# MIPI2HDMI.net
KiCad netlist of a schematic drawn in EAGLE
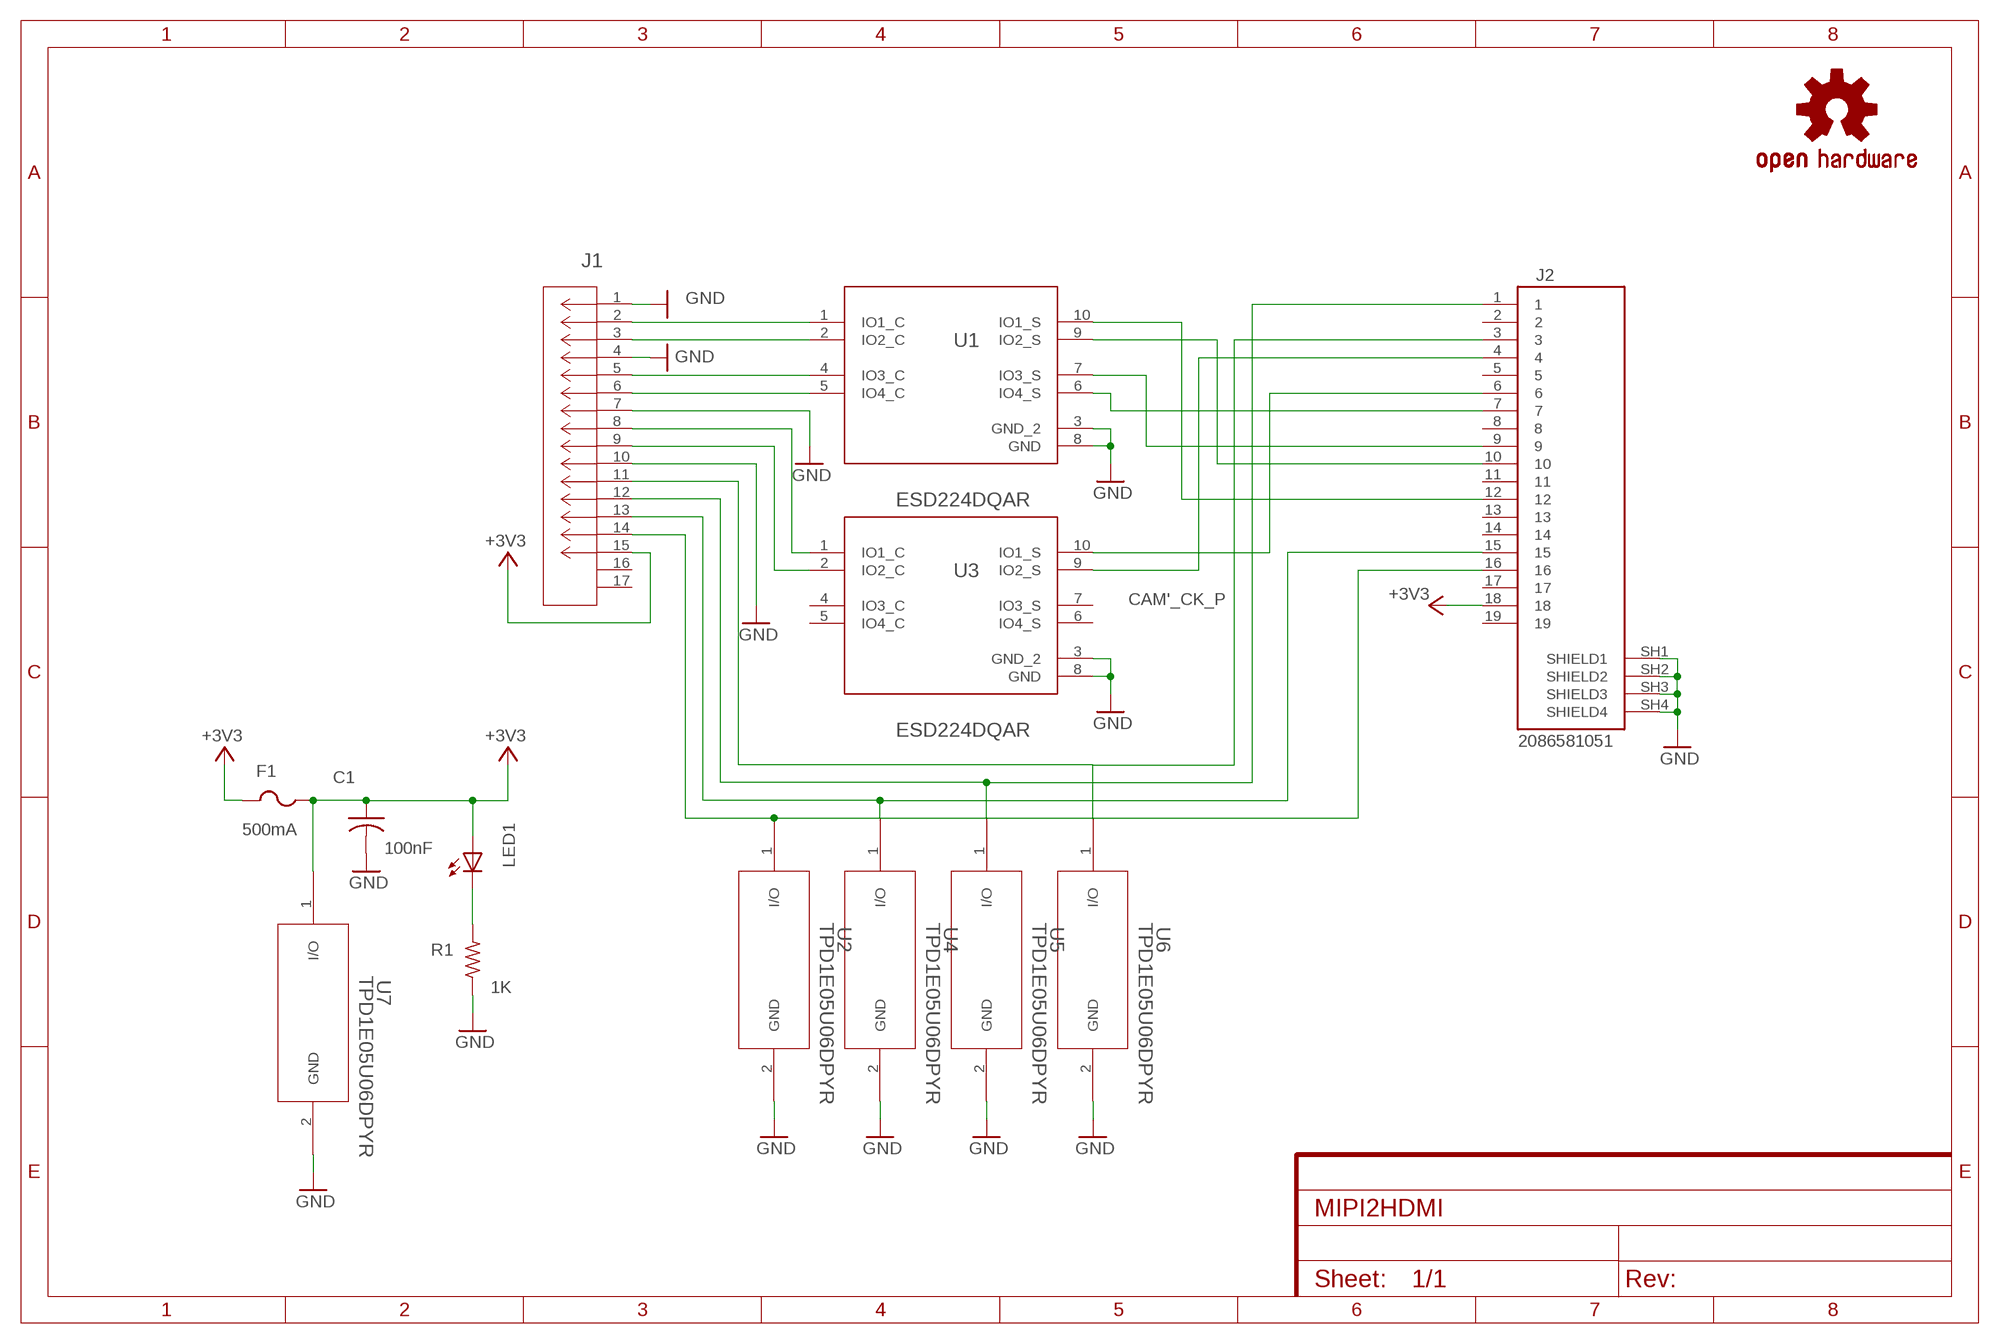
[diagram p0: schematic, sheet 1]

(export (version "E")
  (design (tool "Eeschema 10.0.6"))
  (components
    (comp (ref "C1")
      (value "100nF")
      (footprint "eagle-import:C0603")
      (libsource (lib "eagle-import") (part "C-USC0603"))
    )
    (comp (ref "F1")
      (value "500mA")
      (footprint "eagle-import:R1206")
      (libsource (lib "eagle-import") (part "PTCFUSE-1206"))
    )
    (comp (ref "J1")
      (value "1-84952-5")
      (footprint "eagle-import:CONN15_1-84952-5_TEC")
      (fields (field (name "COPYRIGHT") "Copyright (C) 2024 Ultra Librarian. All rights reserved."))
      (libsource (lib "eagle-import") (part "1-84952-5"))
    )
    (comp (ref "J2")
      (value "2086581051")
      (footprint "eagle-import:MOLEX_2086581051")
      (fields (field (name "MANUFACTURER") "Molex"))
      (libsource (lib "eagle-import") (part "2086581051"))
    )
    (comp (ref "LED1")
      (value "LEDCHIP-LED0603")
      (footprint "eagle-import:CHIP-LED0603")
      (libsource (lib "eagle-import") (part "LEDCHIP-LED0603"))
    )
    (comp (ref "LOGO1")
      (value "OSHW-LOGOM")
      (footprint "eagle-import:OSHW-LOGO-M")
      (libsource (lib "eagle-import") (part "OSHW-LOGOM"))
    )
    (comp (ref "R1")
      (value "1K")
      (footprint "eagle-import:R0603")
      (libsource (lib "eagle-import") (part "R-US_R0603"))
    )
    (comp (ref "U1")
      (value "ESD224DQAR")
      (footprint "eagle-import:DQA0010A")
      (fields (field (name "COPYRIGHT") "Copyright (C) 2024 Ultra Librarian. All rights reserved."))
      (libsource (lib "eagle-import") (part "ESD224DQAR"))
    )
    (comp (ref "U2")
      (value "TPD1E05U06DPYR")
      (footprint "eagle-import:DPY2_TEX")
      (fields (field (name "COPYRIGHT") "Copyright (C) 2024 Ultra Librarian. All rights reserved."))
      (libsource (lib "eagle-import") (part "TPD1E05U06DPYR"))
    )
    (comp (ref "U3")
      (value "ESD224DQAR")
      (footprint "eagle-import:DQA0010A")
      (fields (field (name "COPYRIGHT") "Copyright (C) 2024 Ultra Librarian. All rights reserved."))
      (libsource (lib "eagle-import") (part "ESD224DQAR"))
    )
    (comp (ref "U4")
      (value "TPD1E05U06DPYR")
      (footprint "eagle-import:DPY2_TEX")
      (fields (field (name "COPYRIGHT") "Copyright (C) 2024 Ultra Librarian. All rights reserved."))
      (libsource (lib "eagle-import") (part "TPD1E05U06DPYR"))
    )
    (comp (ref "U5")
      (value "TPD1E05U06DPYR")
      (footprint "eagle-import:DPY2_TEX")
      (fields (field (name "COPYRIGHT") "Copyright (C) 2024 Ultra Librarian. All rights reserved."))
      (libsource (lib "eagle-import") (part "TPD1E05U06DPYR"))
    )
    (comp (ref "U6")
      (value "TPD1E05U06DPYR")
      (footprint "eagle-import:DPY2_TEX")
      (fields (field (name "COPYRIGHT") "Copyright (C) 2024 Ultra Librarian. All rights reserved."))
      (libsource (lib "eagle-import") (part "TPD1E05U06DPYR"))
    )
    (comp (ref "U7")
      (value "TPD1E05U06DPYR")
      (footprint "eagle-import:DPY2_TEX")
      (fields (field (name "COPYRIGHT") "Copyright (C) 2024 Ultra Librarian. All rights reserved."))
      (libsource (lib "eagle-import") (part "TPD1E05U06DPYR"))
    )
  )
  (nets
    (net (code "1") (name "+3V3") (class "Default")
      (node (ref "C1") (pin "1") (pinfunction "1_1") (pintype "passive"))
      (node (ref "F1") (pin "1") (pinfunction "1_1") (pintype "passive"))
      (node (ref "F1") (pin "2") (pinfunction "2_2") (pintype "passive"))
      (node (ref "J1") (pin "15") (pinfunction "15_15") (pintype "passive"))
      (node (ref "J2") (pin "18") (pinfunction "18_18") (pintype "bidirectional"))
      (node (ref "LED1") (pin "A") (pinfunction "A_A") (pintype "passive"))
      (node (ref "U7") (pin "1") (pinfunction "I/O_1") (pintype "bidirectional"))
    )
    (net (code "2") (name "/CAM'_CK_P") (class "Default")
      (node (ref "J2") (pin "4") (pinfunction "4_4") (pintype "bidirectional"))
      (node (ref "U3") (pin "9") (pinfunction "IO2_S_9") (pintype "bidirectional"))
    )
    (net (code "3") (name "GND") (class "Default")
      (node (ref "C1") (pin "2") (pinfunction "2_2") (pintype "passive"))
      (node (ref "J1") (pin "1") (pinfunction "1_1") (pintype "passive"))
      (node (ref "J1") (pin "10") (pinfunction "10_10") (pintype "passive"))
      (node (ref "J1") (pin "4") (pinfunction "4_4") (pintype "passive"))
      (node (ref "J1") (pin "7") (pinfunction "7_7") (pintype "passive"))
      (node (ref "J2") (pin "SH1") (pinfunction "SHIELD1_SH1") (pintype "passive"))
      (node (ref "J2") (pin "SH2") (pinfunction "SHIELD2_SH2") (pintype "passive"))
      (node (ref "J2") (pin "SH3") (pinfunction "SHIELD3_SH3") (pintype "passive"))
      (node (ref "J2") (pin "SH4") (pinfunction "SHIELD4_SH4") (pintype "passive"))
      (node (ref "R1") (pin "1") (pinfunction "1_1") (pintype "passive"))
      (node (ref "U1") (pin "3") (pinfunction "GND_2_3") (pintype "power_in"))
      (node (ref "U1") (pin "8") (pinfunction "GND_8") (pintype "power_in"))
      (node (ref "U2") (pin "2") (pinfunction "GND_2") (pintype "power_in"))
      (node (ref "U3") (pin "3") (pinfunction "GND_2_3") (pintype "power_in"))
      (node (ref "U3") (pin "8") (pinfunction "GND_8") (pintype "power_in"))
      (node (ref "U4") (pin "2") (pinfunction "GND_2") (pintype "power_in"))
      (node (ref "U5") (pin "2") (pinfunction "GND_2") (pintype "power_in"))
      (node (ref "U6") (pin "2") (pinfunction "GND_2") (pintype "power_in"))
      (node (ref "U7") (pin "2") (pinfunction "GND_2") (pintype "power_in"))
    )
    (net (code "4") (name "Net-(LED1-PadC)") (class "Default")
      (node (ref "LED1") (pin "C") (pinfunction "C_C") (pintype "passive"))
      (node (ref "R1") (pin "2") (pinfunction "2_2") (pintype "passive"))
    )
    (net (code "5") (name "Net-(U1-IO1_C)") (class "Default")
      (node (ref "J1") (pin "2") (pinfunction "2_2") (pintype "passive"))
      (node (ref "U1") (pin "1") (pinfunction "IO1_C_1") (pintype "bidirectional"))
    )
    (net (code "6") (name "Net-(U1-IO1_S)") (class "Default")
      (node (ref "J2") (pin "12") (pinfunction "12_12") (pintype "bidirectional"))
      (node (ref "U1") (pin "10") (pinfunction "IO1_S_10") (pintype "bidirectional"))
    )
    (net (code "7") (name "Net-(U1-IO2_C)") (class "Default")
      (node (ref "J1") (pin "3") (pinfunction "3_3") (pintype "passive"))
      (node (ref "U1") (pin "2") (pinfunction "IO2_C_2") (pintype "bidirectional"))
    )
    (net (code "8") (name "Net-(U1-IO2_S)") (class "Default")
      (node (ref "J2") (pin "10") (pinfunction "10_10") (pintype "bidirectional"))
      (node (ref "U1") (pin "9") (pinfunction "IO2_S_9") (pintype "bidirectional"))
    )
    (net (code "9") (name "Net-(U1-IO3_C)") (class "Default")
      (node (ref "J1") (pin "5") (pinfunction "5_5") (pintype "passive"))
      (node (ref "U1") (pin "4") (pinfunction "IO3_C_4") (pintype "bidirectional"))
    )
    (net (code "10") (name "Net-(U1-IO3_S)") (class "Default")
      (node (ref "J2") (pin "9") (pinfunction "9_9") (pintype "bidirectional"))
      (node (ref "U1") (pin "7") (pinfunction "IO3_S_7") (pintype "bidirectional"))
    )
    (net (code "11") (name "Net-(U1-IO4_C)") (class "Default")
      (node (ref "J1") (pin "6") (pinfunction "6_6") (pintype "passive"))
      (node (ref "U1") (pin "5") (pinfunction "IO4_C_5") (pintype "bidirectional"))
    )
    (net (code "12") (name "Net-(U1-IO4_S)") (class "Default")
      (node (ref "J2") (pin "7") (pinfunction "7_7") (pintype "bidirectional"))
      (node (ref "U1") (pin "6") (pinfunction "IO4_S_6") (pintype "bidirectional"))
    )
    (net (code "13") (name "Net-(U2-I{slash}O)") (class "Default")
      (node (ref "J1") (pin "14") (pinfunction "14_14") (pintype "passive"))
      (node (ref "J2") (pin "16") (pinfunction "16_16") (pintype "bidirectional"))
      (node (ref "U2") (pin "1") (pinfunction "I/O_1") (pintype "bidirectional"))
    )
    (net (code "14") (name "Net-(U3-IO1_C)") (class "Default")
      (node (ref "J1") (pin "8") (pinfunction "8_8") (pintype "passive"))
      (node (ref "U3") (pin "1") (pinfunction "IO1_C_1") (pintype "bidirectional"))
    )
    (net (code "15") (name "Net-(U3-IO1_S)") (class "Default")
      (node (ref "J2") (pin "6") (pinfunction "6_6") (pintype "bidirectional"))
      (node (ref "U3") (pin "10") (pinfunction "IO1_S_10") (pintype "bidirectional"))
    )
    (net (code "16") (name "Net-(U3-IO2_C)") (class "Default")
      (node (ref "J1") (pin "9") (pinfunction "9_9") (pintype "passive"))
      (node (ref "U3") (pin "2") (pinfunction "IO2_C_2") (pintype "bidirectional"))
    )
    (net (code "17") (name "Net-(U4-I{slash}O)") (class "Default")
      (node (ref "J1") (pin "13") (pinfunction "13_13") (pintype "passive"))
      (node (ref "J2") (pin "15") (pinfunction "15_15") (pintype "bidirectional"))
      (node (ref "U4") (pin "1") (pinfunction "I/O_1") (pintype "bidirectional"))
    )
    (net (code "18") (name "Net-(U5-I{slash}O)") (class "Default")
      (node (ref "J1") (pin "12") (pinfunction "12_12") (pintype "passive"))
      (node (ref "J2") (pin "1") (pinfunction "1_1") (pintype "bidirectional"))
      (node (ref "U5") (pin "1") (pinfunction "I/O_1") (pintype "bidirectional"))
    )
    (net (code "19") (name "Net-(U6-I{slash}O)") (class "Default")
      (node (ref "J1") (pin "11") (pinfunction "11_11") (pintype "passive"))
      (node (ref "J2") (pin "3") (pinfunction "3_3") (pintype "bidirectional"))
      (node (ref "U6") (pin "1") (pinfunction "I/O_1") (pintype "bidirectional"))
    )
    (net (code "20") (name "unconnected-(J1-Pad16)") (class "Default")
      (node (ref "J1") (pin "16") (pinfunction "16_16") (pintype "passive"))
    )
    (net (code "21") (name "unconnected-(J1-Pad17)") (class "Default")
      (node (ref "J1") (pin "17") (pinfunction "17_17") (pintype "passive"))
    )
    (net (code "22") (name "unconnected-(J2-Pad2)") (class "Default")
      (node (ref "J2") (pin "2") (pinfunction "2_2") (pintype "bidirectional"))
    )
    (net (code "23") (name "unconnected-(J2-Pad5)") (class "Default")
      (node (ref "J2") (pin "5") (pinfunction "5_5") (pintype "bidirectional"))
    )
    (net (code "24") (name "unconnected-(J2-Pad8)") (class "Default")
      (node (ref "J2") (pin "8") (pinfunction "8_8") (pintype "bidirectional"))
    )
    (net (code "25") (name "unconnected-(J2-Pad11)") (class "Default")
      (node (ref "J2") (pin "11") (pinfunction "11_11") (pintype "bidirectional"))
    )
    (net (code "26") (name "unconnected-(J2-Pad13)") (class "Default")
      (node (ref "J2") (pin "13") (pinfunction "13_13") (pintype "bidirectional"))
    )
    (net (code "27") (name "unconnected-(J2-Pad14)") (class "Default")
      (node (ref "J2") (pin "14") (pinfunction "14_14") (pintype "bidirectional"))
    )
    (net (code "28") (name "unconnected-(J2-Pad17)") (class "Default")
      (node (ref "J2") (pin "17") (pinfunction "17_17") (pintype "bidirectional"))
    )
    (net (code "29") (name "unconnected-(J2-Pad19)") (class "Default")
      (node (ref "J2") (pin "19") (pinfunction "19_19") (pintype "bidirectional"))
    )
    (net (code "30") (name "unconnected-(U3-IO3_C-Pad4)") (class "Default")
      (node (ref "U3") (pin "4") (pinfunction "IO3_C_4") (pintype "bidirectional"))
    )
    (net (code "31") (name "unconnected-(U3-IO3_S-Pad7)") (class "Default")
      (node (ref "U3") (pin "7") (pinfunction "IO3_S_7") (pintype "bidirectional"))
    )
    (net (code "32") (name "unconnected-(U3-IO4_C-Pad5)") (class "Default")
      (node (ref "U3") (pin "5") (pinfunction "IO4_C_5") (pintype "bidirectional"))
    )
    (net (code "33") (name "unconnected-(U3-IO4_S-Pad6)") (class "Default")
      (node (ref "U3") (pin "6") (pinfunction "IO4_S_6") (pintype "bidirectional"))
    )
  )
)
